# Power.net
KiCad netlist of a schematic drawn in Altium Designer
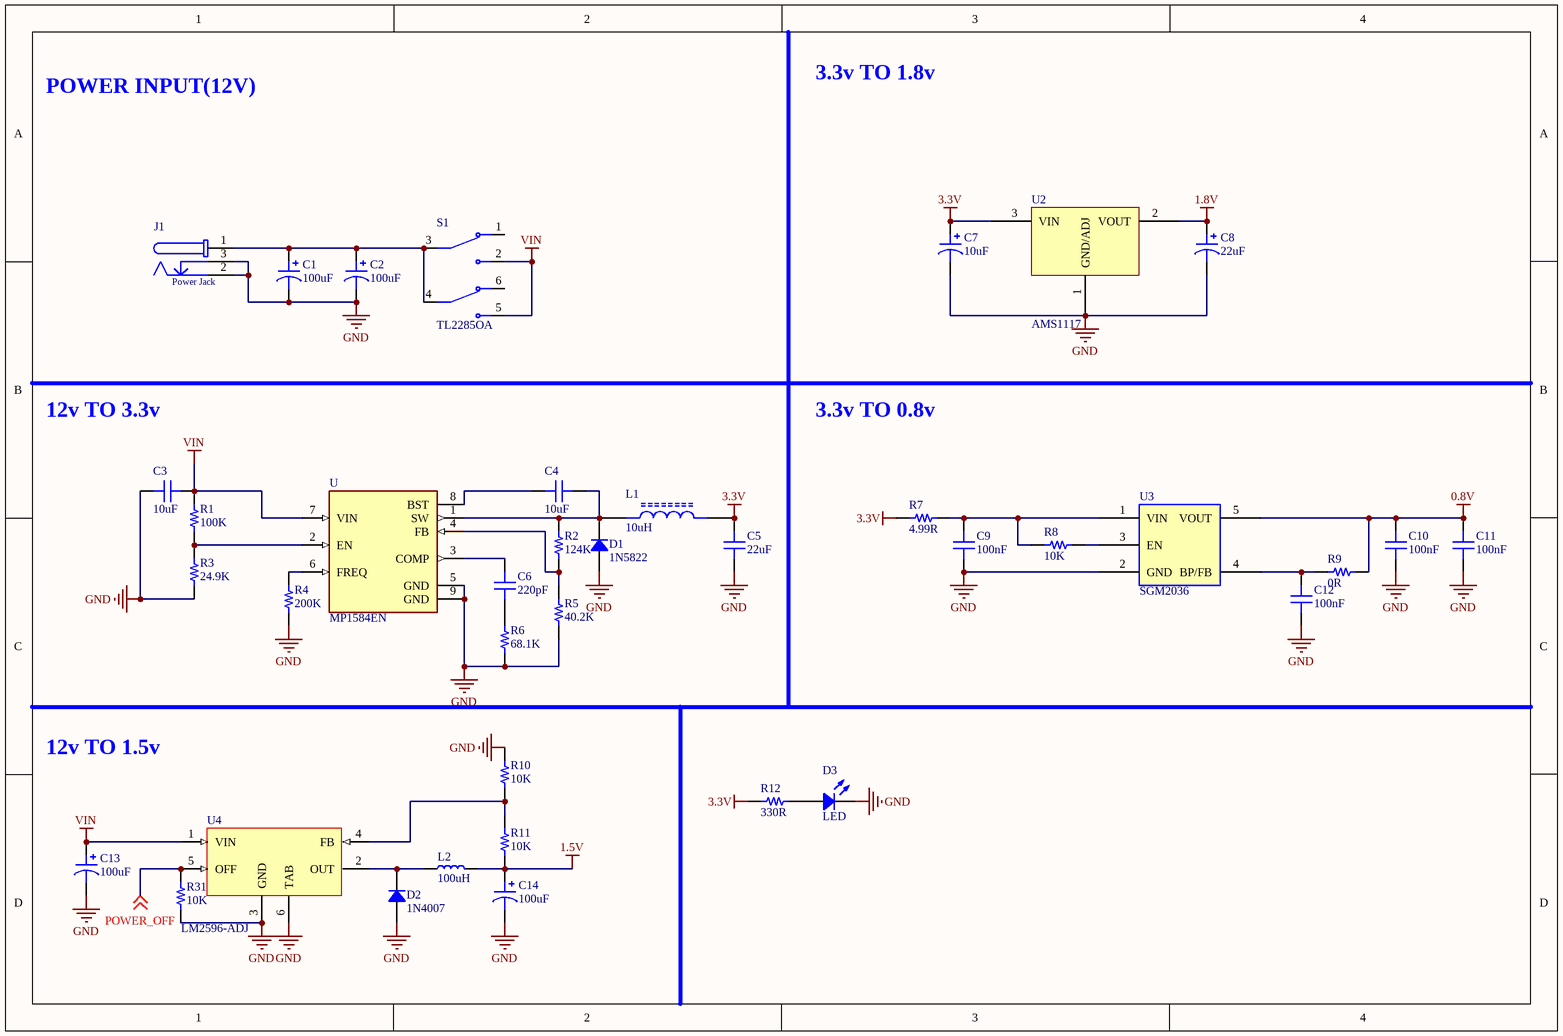
[diagram p0: Power.SchDoc]

(export (version "E")
  (design (tool "Eeschema 10.0.6"))
  (components
    (comp (ref "C1")
      (value "100uF")
      (footprint "CAP ALUM 10.3MM")
      (libsource (lib "Chip_Tester") (part "POLARIZED CAP"))
    )
    (comp (ref "C2")
      (value "100uF")
      (footprint "CAP ALUM 10.3MM")
      (libsource (lib "Chip_Tester") (part "POLARIZED CAP"))
    )
    (comp (ref "C3") (value "10uF") (footprint "CAP-SMD-1206") (libsource (lib "Chip_Tester") (part "CAP")))
    (comp (ref "C4") (value "10uF") (footprint "CAP-SMD-1206") (libsource (lib "Chip_Tester") (part "CAP")))
    (comp (ref "C5") (value "22uF") (footprint "CAP-SMD-1206") (libsource (lib "Chip_Tester") (part "CAP")))
    (comp (ref "C6") (value "220pF") (footprint "CAP-SMD-1206") (libsource (lib "Chip_Tester") (part "CAP")))
    (comp (ref "C7")
      (value "10uF")
      (footprint "CAP-TAN-CASE-A")
      (libsource (lib "Chip_Tester") (part "POLARIZED CAP"))
    )
    (comp (ref "C8")
      (value "22uF")
      (footprint "CAP-TAN-CASE-A")
      (libsource (lib "Chip_Tester") (part "POLARIZED CAP"))
    )
    (comp (ref "C9") (value "100nF") (footprint "CAP-SMD-1206") (libsource (lib "Chip_Tester") (part "CAP")))
    (comp (ref "C10") (value "100nF") (footprint "CAP-SMD-1206") (libsource (lib "Chip_Tester") (part "CAP")))
    (comp (ref "C11") (value "100nF") (footprint "CAP-SMD-1206") (libsource (lib "Chip_Tester") (part "CAP")))
    (comp (ref "C12") (value "100nF") (footprint "CAP-SMD-1206") (libsource (lib "Chip_Tester") (part "CAP")))
    (comp (ref "C13")
      (value "100uF")
      (footprint "CAP-TAN-CASE-E")
      (libsource (lib "Chip_Tester") (part "POLARIZED CAP"))
    )
    (comp (ref "C14")
      (value "100uF")
      (footprint "CAP-TAN-CASE-E")
      (libsource (lib "Chip_Tester") (part "POLARIZED CAP"))
    )
    (comp (ref "D1") (value "1N5822") (footprint "m7") (libsource (lib "Chip_Tester") (part "1N4007")))
    (comp (ref "D2") (value "1N4007") (footprint "m7") (libsource (lib "Chip_Tester") (part "1N4007")))
    (comp (ref "D3") (value "LED") (footprint "LED_0805_RED") (libsource (lib "Chip_Tester") (part "LED")))
    (comp (ref "J1")
      (value "Power Jack")
      (footprint "DC-Jack-THT-RA-6.4")
      (description "DC Power Jack Connector Low Profile with 4 soldering pads")
      (libsource (lib "Chip_Tester") (part "DC-JACK"))
    )
    (comp (ref "L1")
      (value "10uH")
      (footprint "SRN6045TA")
      (description "3.3µH Semi-Shielded Wirewound Inductor 5A 21mOhm Nonstandard")
      (libsource (lib "Chip_Tester") (part "SRN6045TA-3R3Y"))
    )
    (comp (ref "L2") (value "100uH") (footprint "inductor") (libsource (lib "Chip_Tester") (part "inductor")))
    (comp (ref "R1") (value "100K") (footprint "RES-SMD-0805") (libsource (lib "Chip_Tester") (part "RES")))
    (comp (ref "R2") (value "124K") (footprint "RES-SMD-0805") (libsource (lib "Chip_Tester") (part "RES")))
    (comp (ref "R3") (value "24.9K") (footprint "RES-SMD-0805") (libsource (lib "Chip_Tester") (part "RES")))
    (comp (ref "R4") (value "200K") (footprint "RES-SMD-0805") (libsource (lib "Chip_Tester") (part "RES")))
    (comp (ref "R5") (value "40.2K") (footprint "RES-SMD-0805") (libsource (lib "Chip_Tester") (part "RES")))
    (comp (ref "R6") (value "68.1K") (footprint "RES-SMD-0805") (libsource (lib "Chip_Tester") (part "RES")))
    (comp (ref "R7") (value "4.99R") (footprint "RES-SMD-0805") (libsource (lib "Chip_Tester") (part "RES")))
    (comp (ref "R8") (value "10K") (footprint "RES-SMD-0805") (libsource (lib "Chip_Tester") (part "RES")))
    (comp (ref "R9") (value "0R") (footprint "RES-SMD-0805") (libsource (lib "Chip_Tester") (part "RES")))
    (comp (ref "R10") (value "10K") (footprint "RES-SMD-0805") (libsource (lib "Chip_Tester") (part "RES")))
    (comp (ref "R11") (value "10K") (footprint "RES-SMD-0805") (libsource (lib "Chip_Tester") (part "RES")))
    (comp (ref "R12") (value "330R") (footprint "RES-SMD-0805") (libsource (lib "Chip_Tester") (part "RES")))
    (comp (ref "R31") (value "10K") (footprint "RES-SMD-0805") (libsource (lib "Chip_Tester") (part "RES")))
    (comp (ref "S1")
      (value "TL2285OA")
      (footprint "SW_TL2285OA")
      (description "Pushbutton Switch DPDT Standard Through Hole")
      (fields (field (name "MF") "E-Switch"))
      (libsource (lib "Chip_Tester") (part "TL2285OA"))
    )
    (comp (ref "U")
      (value "MP1584EN")
      (footprint "control:SOIC127P600X170-9N")
      (fields (field (name "MF") "Monolithic Power"))
      (libsource (lib "Chip_Tester") (part "MP1584EN"))
    )
    (comp (ref "U2")
      (value "AMS1117")
      (footprint "AMS1117")
      (description "AMS1117 1A LOW DROPOUT VOLTAGE REGULATOR")
      (libsource (lib "Chip_Tester") (part "AMS1117"))
    )
    (comp (ref "U3")
      (value "SGM2036")
      (footprint "SOT23-5PIN")
      (libsource (lib "Chip_Tester") (part "SGM2036"))
    )
    (comp (ref "U4")
      (value "LM2596-ADJ")
      (footprint "LM2576")
      (description "SIMPLE SWITCHER® 40V, 3A Low Component Count Step-Down Regulator 5-DDPAK/TO-263 -40 to 125")
      (fields
        (field (name "MANUFACTURER") "TI National Semiconductor")
        (field (name "MANUFACTURER PART NUMBER") "LM2576S-5.0/NOPB")
      )
      (libsource (lib "Chip_Tester") (part "LM2576S-5.0"))
    )
  )
  (nets
    (net (code "1") (name "0.8V") (class "Default")
      (node (ref "C10") (pin "2") (pinfunction "2_2") (pintype "passive"))
      (node (ref "C11") (pin "2") (pinfunction "2_2") (pintype "passive"))
      (node (ref "R9") (pin "1") (pinfunction "1_1") (pintype "passive"))
      (node (ref "U3") (pin "5") (pinfunction "VOUT_5") (pintype "passive"))
    )
    (net (code "2") (name "1.5V") (class "Default")
      (node (ref "C14") (pin "1") (pinfunction "1_1") (pintype "passive"))
      (node (ref "L2") (pin "2") (pinfunction "2_2") (pintype "passive"))
      (node (ref "R11") (pin "2") (pinfunction "2_2") (pintype "passive"))
    )
    (net (code "3") (name "1.8V") (class "Default")
      (node (ref "C8") (pin "1") (pinfunction "1_1") (pintype "passive"))
      (node (ref "U2") (pin "2") (pinfunction "VOUT_2") (pintype "passive"))
    )
    (net (code "4") (name "3.3V") (class "Default")
      (node (ref "C5") (pin "2") (pinfunction "2_2") (pintype "passive"))
      (node (ref "C7") (pin "1") (pinfunction "1_1") (pintype "passive"))
      (node (ref "L1") (pin "2") (pinfunction "2_2") (pintype "passive"))
      (node (ref "R12") (pin "2") (pinfunction "2_2") (pintype "passive"))
      (node (ref "R7") (pin "2") (pinfunction "2_2") (pintype "passive"))
      (node (ref "U2") (pin "3") (pinfunction "VIN_3") (pintype "passive"))
    )
    (net (code "5") (name "GND") (class "Default")
      (node (ref "C1") (pin "2") (pinfunction "2_2") (pintype "passive"))
      (node (ref "C10") (pin "1") (pinfunction "1_1") (pintype "passive"))
      (node (ref "C11") (pin "1") (pinfunction "1_1") (pintype "passive"))
      (node (ref "C12") (pin "1") (pinfunction "1_1") (pintype "passive"))
      (node (ref "C13") (pin "2") (pinfunction "2_2") (pintype "passive"))
      (node (ref "C14") (pin "2") (pinfunction "2_2") (pintype "passive"))
      (node (ref "C2") (pin "2") (pinfunction "2_2") (pintype "passive"))
      (node (ref "C3") (pin "1") (pinfunction "1_1") (pintype "passive"))
      (node (ref "C5") (pin "1") (pinfunction "1_1") (pintype "passive"))
      (node (ref "C7") (pin "2") (pinfunction "2_2") (pintype "passive"))
      (node (ref "C8") (pin "2") (pinfunction "2_2") (pintype "passive"))
      (node (ref "C9") (pin "1") (pinfunction "1_1") (pintype "passive"))
      (node (ref "D1") (pin "1") (pinfunction "1_1") (pintype "passive"))
      (node (ref "D2") (pin "1") (pinfunction "1_1") (pintype "passive"))
      (node (ref "D3") (pin "2") (pinfunction "2_2") (pintype "passive"))
      (node (ref "J1") (pin "2") (pinfunction "2_2") (pintype "passive"))
      (node (ref "J1") (pin "3") (pinfunction "3_3") (pintype "passive"))
      (node (ref "R10") (pin "1") (pinfunction "1_1") (pintype "passive"))
      (node (ref "R3") (pin "1") (pinfunction "1_1") (pintype "passive"))
      (node (ref "R31") (pin "2") (pinfunction "2_2") (pintype "passive"))
      (node (ref "R4") (pin "1") (pinfunction "1_1") (pintype "passive"))
      (node (ref "R5") (pin "1") (pinfunction "1_1") (pintype "passive"))
      (node (ref "R6") (pin "1") (pinfunction "1_1") (pintype "passive"))
      (node (ref "U") (pin "5") (pinfunction "GND_5") (pintype "power_in"))
      (node (ref "U") (pin "9") (pinfunction "GND_9") (pintype "power_in"))
      (node (ref "U2") (pin "1") (pinfunction "GND/ADJ_1") (pintype "passive"))
      (node (ref "U3") (pin "2") (pinfunction "GND_2") (pintype "passive"))
      (node (ref "U4") (pin "3") (pinfunction "GND_3") (pintype "power_in"))
      (node (ref "U4") (pin "6") (pinfunction "TAB_6") (pintype "passive"))
    )
    (net (code "6") (name "Net-(C6-Pad1)") (class "Default")
      (node (ref "C6") (pin "1") (pinfunction "1_1") (pintype "passive"))
      (node (ref "R6") (pin "2") (pinfunction "2_2") (pintype "passive"))
    )
    (net (code "7") (name "Net-(D3-Pad1)") (class "Default")
      (node (ref "D3") (pin "1") (pinfunction "1_1") (pintype "passive"))
      (node (ref "R12") (pin "1") (pinfunction "1_1") (pintype "passive"))
    )
    (net (code "8") (name "Net-(S1-COM1)") (class "Default")
      (node (ref "C1") (pin "1") (pinfunction "1_1") (pintype "passive"))
      (node (ref "C2") (pin "1") (pinfunction "1_1") (pintype "passive"))
      (node (ref "J1") (pin "1") (pinfunction "1_1") (pintype "passive"))
      (node (ref "S1") (pin "3") (pinfunction "COM1_3") (pintype "passive"))
      (node (ref "S1") (pin "4") (pinfunction "COM2_4") (pintype "passive"))
    )
    (net (code "9") (name "Net-(U-BST)") (class "Default")
      (node (ref "C4") (pin "1") (pinfunction "1_1") (pintype "passive"))
      (node (ref "U") (pin "8") (pinfunction "BST_8") (pintype "passive"))
    )
    (net (code "10") (name "Net-(U-COMP)") (class "Default")
      (node (ref "C6") (pin "2") (pinfunction "2_2") (pintype "passive"))
      (node (ref "U") (pin "3") (pinfunction "COMP_3") (pintype "output"))
    )
    (net (code "11") (name "Net-(U-EN)") (class "Default")
      (node (ref "R1") (pin "1") (pinfunction "1_1") (pintype "passive"))
      (node (ref "R3") (pin "2") (pinfunction "2_2") (pintype "passive"))
      (node (ref "U") (pin "2") (pinfunction "EN_2") (pintype "input"))
    )
    (net (code "12") (name "Net-(U-FB)") (class "Default")
      (node (ref "R2") (pin "1") (pinfunction "1_1") (pintype "passive"))
      (node (ref "R5") (pin "2") (pinfunction "2_2") (pintype "passive"))
      (node (ref "U") (pin "4") (pinfunction "FB_4") (pintype "input"))
    )
    (net (code "13") (name "Net-(U-FREQ)") (class "Default")
      (node (ref "R4") (pin "2") (pinfunction "2_2") (pintype "passive"))
      (node (ref "U") (pin "6") (pinfunction "FREQ_6") (pintype "input"))
    )
    (net (code "14") (name "Net-(U-SW)") (class "Default")
      (node (ref "C4") (pin "2") (pinfunction "2_2") (pintype "passive"))
      (node (ref "D1") (pin "2") (pinfunction "2_2") (pintype "passive"))
      (node (ref "L1") (pin "1") (pinfunction "1_1") (pintype "passive"))
      (node (ref "R2") (pin "2") (pinfunction "2_2") (pintype "passive"))
      (node (ref "U") (pin "1") (pinfunction "SW_1") (pintype "output"))
    )
    (net (code "15") (name "Net-(U3-BP{slash}FB)") (class "Default")
      (node (ref "C12") (pin "2") (pinfunction "2_2") (pintype "passive"))
      (node (ref "R9") (pin "2") (pinfunction "2_2") (pintype "passive"))
      (node (ref "U3") (pin "4") (pinfunction "BP/FB_4") (pintype "passive"))
    )
    (net (code "16") (name "Net-(U3-EN)") (class "Default")
      (node (ref "R8") (pin "1") (pinfunction "1_1") (pintype "passive"))
      (node (ref "U3") (pin "3") (pinfunction "EN_3") (pintype "passive"))
    )
    (net (code "17") (name "Net-(U3-VIN)") (class "Default")
      (node (ref "C9") (pin "2") (pinfunction "2_2") (pintype "passive"))
      (node (ref "R7") (pin "1") (pinfunction "1_1") (pintype "passive"))
      (node (ref "R8") (pin "2") (pinfunction "2_2") (pintype "passive"))
      (node (ref "U3") (pin "1") (pinfunction "VIN_1") (pintype "passive"))
    )
    (net (code "18") (name "Net-(U4-FB)") (class "Default")
      (node (ref "R10") (pin "2") (pinfunction "2_2") (pintype "passive"))
      (node (ref "R11") (pin "1") (pinfunction "1_1") (pintype "passive"))
      (node (ref "U4") (pin "4") (pinfunction "FB_4") (pintype "input"))
    )
    (net (code "19") (name "Net-(U4-OUT)") (class "Default")
      (node (ref "D2") (pin "2") (pinfunction "2_2") (pintype "passive"))
      (node (ref "L2") (pin "1") (pinfunction "1_1") (pintype "passive"))
      (node (ref "U4") (pin "2") (pinfunction "OUT_2") (pintype "power_in"))
    )
    (net (code "20") (name "POWER_OFF") (class "Default")
      (node (ref "R31") (pin "1") (pinfunction "1_1") (pintype "passive"))
      (node (ref "U4") (pin "5") (pinfunction "OFF_5") (pintype "input"))
    )
    (net (code "21") (name "VIN") (class "Default")
      (node (ref "C13") (pin "1") (pinfunction "1_1") (pintype "passive"))
      (node (ref "C3") (pin "2") (pinfunction "2_2") (pintype "passive"))
      (node (ref "R1") (pin "2") (pinfunction "2_2") (pintype "passive"))
      (node (ref "S1") (pin "2") (pinfunction "NO1_2") (pintype "passive"))
      (node (ref "S1") (pin "5") (pinfunction "NO2_5") (pintype "passive"))
      (node (ref "U") (pin "7") (pinfunction "VIN_7") (pintype "input"))
      (node (ref "U4") (pin "1") (pinfunction "VIN_1") (pintype "input"))
    )
    (net (code "22") (name "unconnected-(S1-NC1-Pad1)") (class "Default")
      (node (ref "S1") (pin "1") (pinfunction "NC1_1") (pintype "passive"))
    )
    (net (code "23") (name "unconnected-(S1-NC2-Pad6)") (class "Default")
      (node (ref "S1") (pin "6") (pinfunction "NC2_6") (pintype "passive"))
    )
  )
)
